# Driver.net
KiCad netlist of a schematic drawn in EAGLE
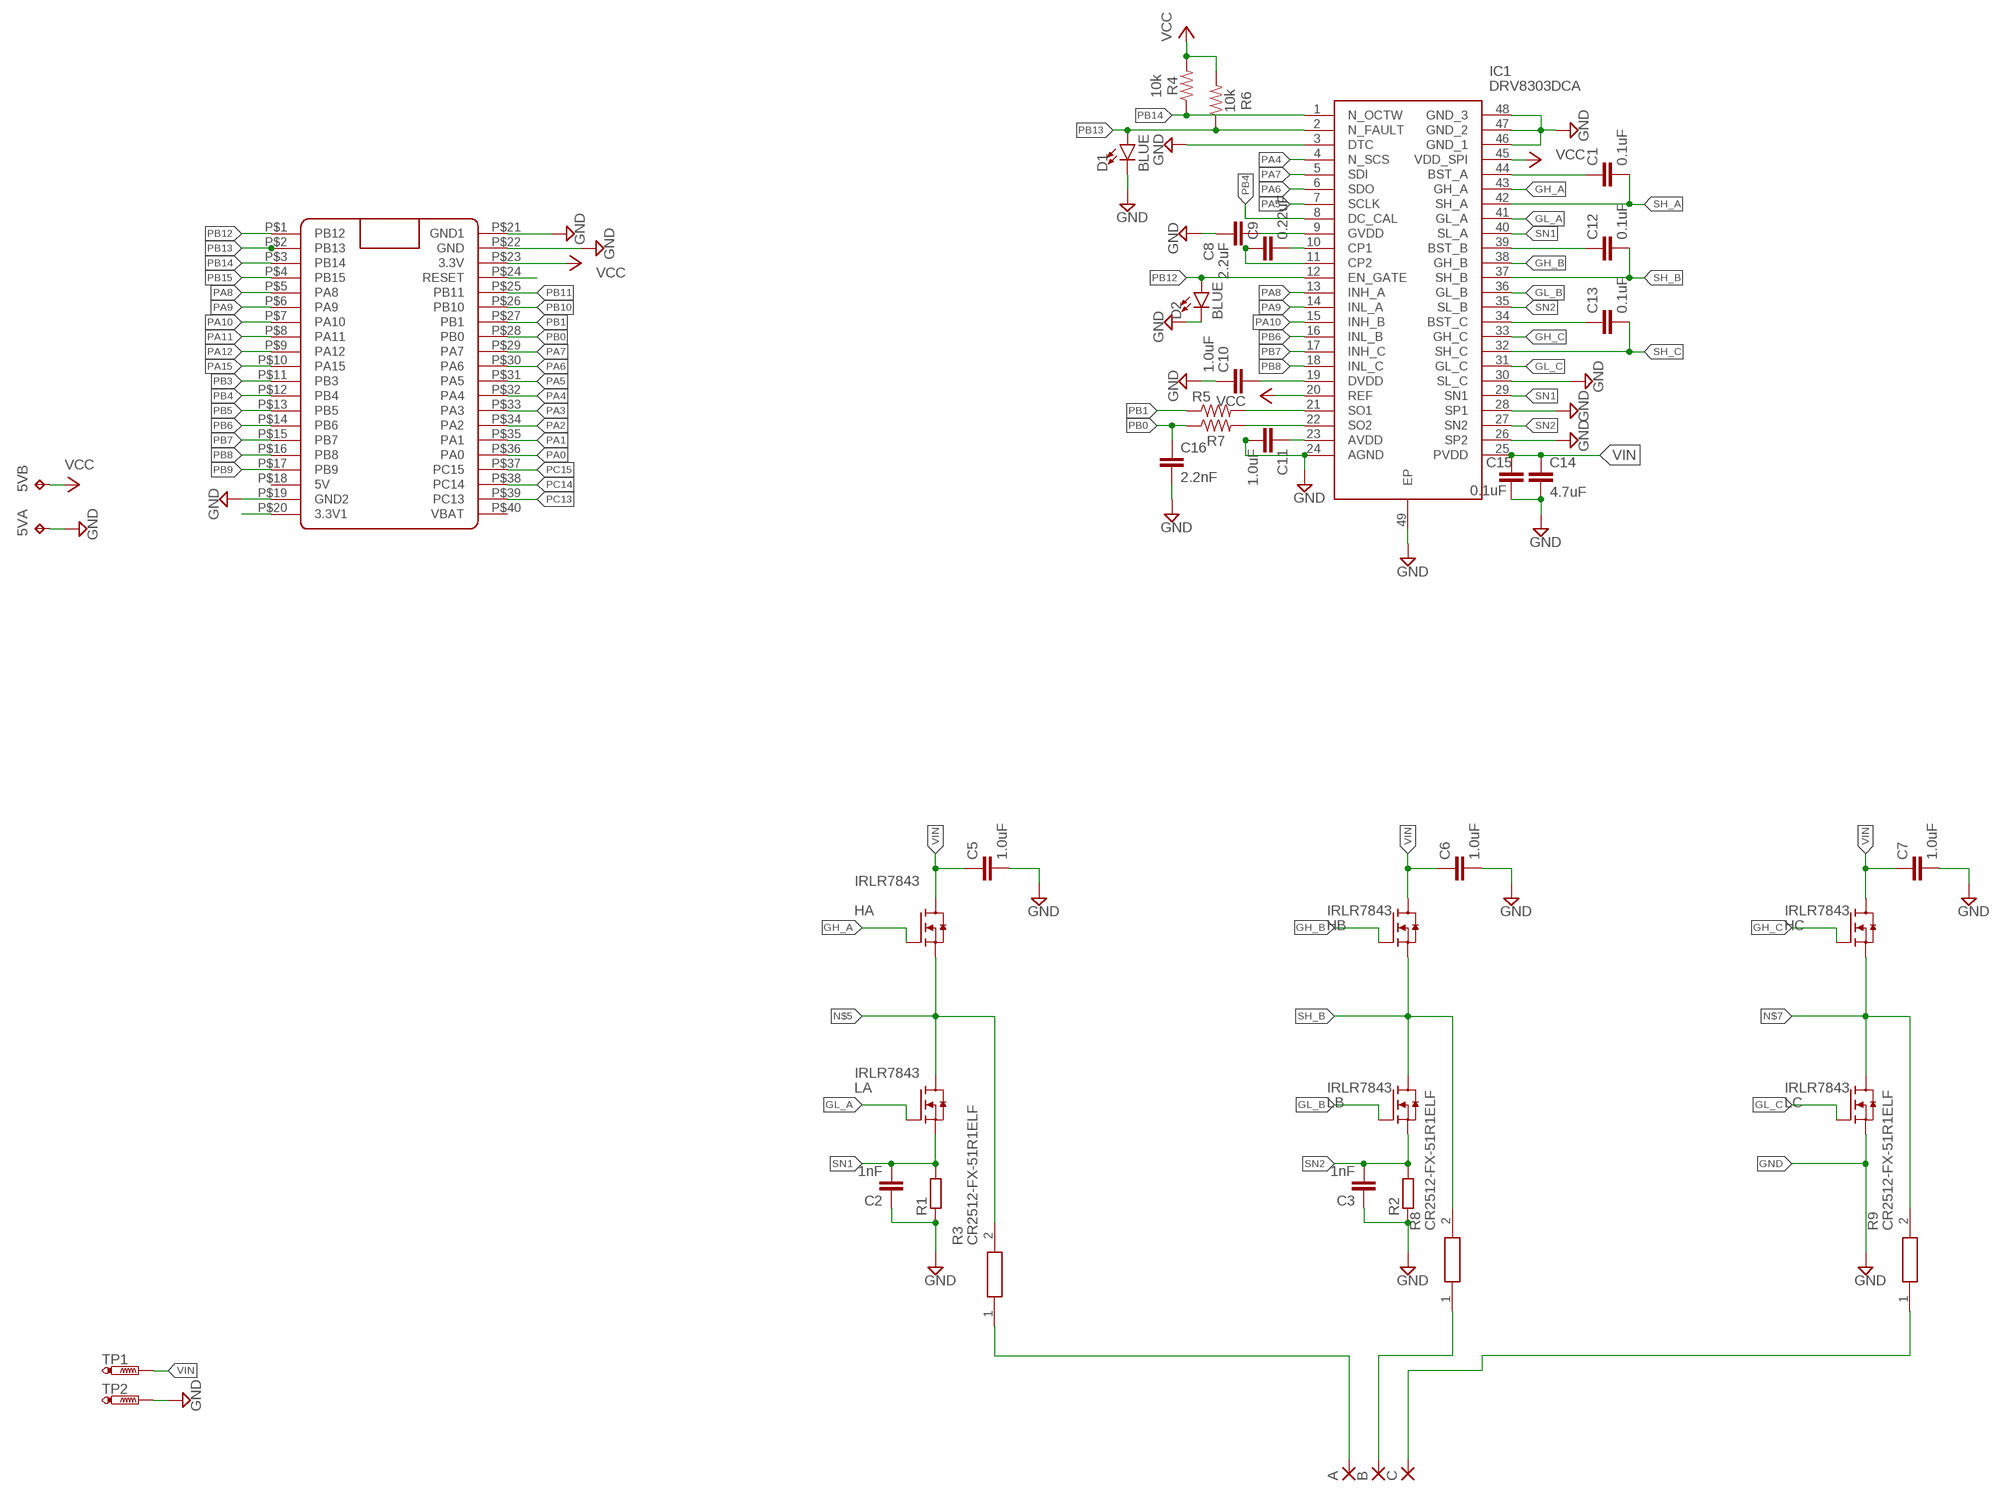
[diagram p0: schematic, sheet 1]

(export (version "E")
  (design (tool "Eeschema 10.0.6"))
  (components
    (comp (ref "5V")
      (value "TP2P2-38-17")
      (footprint "eagle-import:P2-38-17")
      (libsource (lib "eagle-import") (part "TP2P2-38-17"))
    )
    (comp (ref "A")
      (value "SMD5")
      (footprint "eagle-import:SMD2,54-5,08")
      (libsource (lib "eagle-import") (part "SMD5"))
    )
    (comp (ref "B")
      (value "SMD5")
      (footprint "eagle-import:SMD2,54-5,08")
      (libsource (lib "eagle-import") (part "SMD5"))
    )
    (comp (ref "C")
      (value "SMD5")
      (footprint "eagle-import:SMD2,54-5,08")
      (libsource (lib "eagle-import") (part "SMD5"))
    )
    (comp (ref "C1")
      (value "0.1uF")
      (footprint "eagle-import:0603")
      (libsource (lib "eagle-import") (part "0.1UF-0603-25V-(+80/-20%)"))
    )
    (comp (ref "C2")
      (value "1nF")
      (footprint "eagle-import:0603")
      (libsource (lib "eagle-import") (part "1.0NF/1000PF-0603-50V-10%"))
    )
    (comp (ref "C3")
      (value "1nF")
      (footprint "eagle-import:0603")
      (libsource (lib "eagle-import") (part "1.0NF/1000PF-0603-50V-10%"))
    )
    (comp (ref "C5")
      (value "1.0uF")
      (footprint "eagle-import:0603")
      (libsource (lib "eagle-import") (part "1.0UF-0603-16V-10%-X7R"))
    )
    (comp (ref "C6")
      (value "1.0uF")
      (footprint "eagle-import:0603")
      (libsource (lib "eagle-import") (part "1.0UF-0603-16V-10%-X7R"))
    )
    (comp (ref "C7")
      (value "1.0uF")
      (footprint "eagle-import:0603")
      (libsource (lib "eagle-import") (part "1.0UF-0603-16V-10%-X7R"))
    )
    (comp (ref "C8")
      (value "2.2uF")
      (footprint "eagle-import:0603")
      (libsource (lib "eagle-import") (part "2.2UF-0603-10V-20%"))
    )
    (comp (ref "C9")
      (value "0.22uF")
      (footprint "eagle-import:0603")
      (libsource (lib "eagle-import") (part "0.22UF-0603-25V-10%"))
    )
    (comp (ref "C10")
      (value "1.0uF")
      (footprint "eagle-import:0603")
      (libsource (lib "eagle-import") (part "1.0UF-0603-16V-10%"))
    )
    (comp (ref "C11")
      (value "1.0uF")
      (footprint "eagle-import:0603")
      (libsource (lib "eagle-import") (part "1.0UF-0603-16V-10%"))
    )
    (comp (ref "C12")
      (value "0.1uF")
      (footprint "eagle-import:0603")
      (libsource (lib "eagle-import") (part "0.1UF-0603-25V-(+80/-20%)"))
    )
    (comp (ref "C13")
      (value "0.1uF")
      (footprint "eagle-import:0603")
      (libsource (lib "eagle-import") (part "0.1UF-0603-25V-(+80/-20%)"))
    )
    (comp (ref "C14")
      (value "4.7uF")
      (footprint "eagle-import:0603")
      (libsource (lib "eagle-import") (part "4.7UF-0603-35V-(20%)"))
    )
    (comp (ref "C15")
      (value "0.1uF")
      (footprint "eagle-import:0603")
      (libsource (lib "eagle-import") (part "0.1UF-0603-25V-(+80/-20%)"))
    )
    (comp (ref "C16")
      (value "2.2nF")
      (footprint "eagle-import:0603")
      (libsource (lib "eagle-import") (part "2.2NF/2200PF-0603-50V-10%"))
    )
    (comp (ref "D1")
      (value "BLUE")
      (footprint "eagle-import:LED-0603")
      (libsource (lib "eagle-import") (part "LED-BLUE0603"))
    )
    (comp (ref "D2")
      (value "BLUE")
      (footprint "eagle-import:LED-0603")
      (libsource (lib "eagle-import") (part "LED-BLUE0603"))
    )
    (comp (ref "HA")
      (value "IRLR7843")
      (footprint "eagle-import:TO252")
      (libsource (lib "eagle-import") (part "IRLR7843"))
    )
    (comp (ref "HB")
      (value "IRLR7843")
      (footprint "eagle-import:TO252")
      (libsource (lib "eagle-import") (part "IRLR7843"))
    )
    (comp (ref "HC")
      (value "IRLR7843")
      (footprint "eagle-import:TO252")
      (libsource (lib "eagle-import") (part "IRLR7843"))
    )
    (comp (ref "IC1")
      (value "DRV8303DCA")
      (footprint "eagle-import:SOP50P810X120-49N")
      (fields (field (name "MOUSER_PART_NUMBER") "595-DRV8303DCA"))
      (libsource (lib "eagle-import") (part "DRV8303DCA"))
    )
    (comp (ref "LA")
      (value "IRLR7843")
      (footprint "eagle-import:TO252")
      (libsource (lib "eagle-import") (part "IRLR7843"))
    )
    (comp (ref "LB")
      (value "IRLR7843")
      (footprint "eagle-import:TO252")
      (libsource (lib "eagle-import") (part "IRLR7843"))
    )
    (comp (ref "LC")
      (value "IRLR7843")
      (footprint "eagle-import:TO252")
      (libsource (lib "eagle-import") (part "IRLR7843"))
    )
    (comp (ref "R1")
      (value "R-EU_R2512")
      (footprint "eagle-import:R2512")
      (libsource (lib "eagle-import") (part "R-EU_R2512"))
    )
    (comp (ref "R2")
      (value "R-EU_R2512")
      (footprint "eagle-import:R2512")
      (libsource (lib "eagle-import") (part "R-EU_R2512"))
    )
    (comp (ref "R3")
      (value "CR2512-FX-51R1ELF")
      (footprint "eagle-import:RESC6331X75N")
      (fields (field (name "MOUSER_PART_NUMBER") "652-CR2512FX51R1ELF"))
      (libsource (lib "eagle-import") (part "CR2512-FX-51R1ELF"))
    )
    (comp (ref "R4")
      (value "10k")
      (footprint "eagle-import:0603")
      (libsource (lib "eagle-import") (part "10KOHM-0603-1/10W-1%"))
    )
    (comp (ref "R5")
      (value "0")
      (footprint "eagle-import:0603")
      (libsource (lib "eagle-import") (part "0OHM-0603-1/10W"))
    )
    (comp (ref "R6")
      (value "10k")
      (footprint "eagle-import:0603")
      (libsource (lib "eagle-import") (part "10KOHM-0603-1/10W-1%"))
    )
    (comp (ref "R7")
      (value "0")
      (footprint "eagle-import:0603")
      (libsource (lib "eagle-import") (part "0OHM-0603-1/10W"))
    )
    (comp (ref "R8")
      (value "CR2512-FX-51R1ELF")
      (footprint "eagle-import:RESC6331X75N")
      (fields (field (name "MOUSER_PART_NUMBER") "652-CR2512FX51R1ELF"))
      (libsource (lib "eagle-import") (part "CR2512-FX-51R1ELF"))
    )
    (comp (ref "R9")
      (value "CR2512-FX-51R1ELF")
      (footprint "eagle-import:RESC6331X75N")
      (fields (field (name "MOUSER_PART_NUMBER") "652-CR2512FX51R1ELF"))
      (libsource (lib "eagle-import") (part "CR2512-FX-51R1ELF"))
    )
    (comp (ref "TP1")
      (value "PTR1PAD1-20Y")
      (footprint "eagle-import:P1-20Y")
      (libsource (lib "eagle-import") (part "PTR1PAD1-20Y"))
    )
    (comp (ref "TP2")
      (value "PTR1PAD1-20Y")
      (footprint "eagle-import:P1-20Y")
      (libsource (lib "eagle-import") (part "PTR1PAD1-20Y"))
    )
    (comp (ref "U$1")
      (value "BLUE_PILLADVANCED")
      (footprint "eagle-import:BLUE_PILL_ADV")
      (libsource (lib "eagle-import") (part "BLUE_PILLADVANCED"))
    )
  )
  (nets
    (net (code "1") (name "GH_A") (class "Default")
      (node (ref "HA") (pin "1") (pinfunction "G_1") (pintype "passive"))
      (node (ref "IC1") (pin "43") (pinfunction "GH_A_43") (pintype "output"))
    )
    (net (code "2") (name "GH_B") (class "Default")
      (node (ref "HB") (pin "1") (pinfunction "G_1") (pintype "passive"))
      (node (ref "IC1") (pin "38") (pinfunction "GH_B_38") (pintype "output"))
    )
    (net (code "3") (name "GH_C") (class "Default")
      (node (ref "HC") (pin "1") (pinfunction "G_1") (pintype "passive"))
      (node (ref "IC1") (pin "33") (pinfunction "GH_C_33") (pintype "output"))
    )
    (net (code "4") (name "GL_A") (class "Default")
      (node (ref "IC1") (pin "41") (pinfunction "GL_A_41") (pintype "output"))
      (node (ref "LA") (pin "1") (pinfunction "G_1") (pintype "passive"))
    )
    (net (code "5") (name "GL_B") (class "Default")
      (node (ref "IC1") (pin "36") (pinfunction "GL_B_36") (pintype "output"))
      (node (ref "LB") (pin "1") (pinfunction "G_1") (pintype "passive"))
    )
    (net (code "6") (name "GL_C") (class "Default")
      (node (ref "IC1") (pin "31") (pinfunction "GL_C_31") (pintype "output"))
      (node (ref "LC") (pin "1") (pinfunction "G_1") (pintype "passive"))
    )
    (net (code "7") (name "GND") (class "Default")
      (node (ref "5V") (pin "TP-1") (pinfunction "TP_TP-1") (pintype "input"))
      (node (ref "C10") (pin "1") (pinfunction "1_1") (pintype "passive"))
      (node (ref "C11") (pin "2") (pinfunction "2_2") (pintype "passive"))
      (node (ref "C14") (pin "2") (pinfunction "2_2") (pintype "passive"))
      (node (ref "C15") (pin "2") (pinfunction "2_2") (pintype "passive"))
      (node (ref "C16") (pin "2") (pinfunction "2_2") (pintype "passive"))
      (node (ref "C2") (pin "1") (pinfunction "1_1") (pintype "passive"))
      (node (ref "C3") (pin "1") (pinfunction "1_1") (pintype "passive"))
      (node (ref "C5") (pin "2") (pinfunction "2_2") (pintype "passive"))
      (node (ref "C6") (pin "2") (pinfunction "2_2") (pintype "passive"))
      (node (ref "C7") (pin "2") (pinfunction "2_2") (pintype "passive"))
      (node (ref "C8") (pin "2") (pinfunction "2_2") (pintype "passive"))
      (node (ref "D1") (pin "C") (pinfunction "C_C") (pintype "passive"))
      (node (ref "D2") (pin "C") (pinfunction "C_C") (pintype "passive"))
      (node (ref "IC1") (pin "24") (pinfunction "AGND_24") (pintype "power_in"))
      (node (ref "IC1") (pin "26") (pinfunction "SP2_26") (pintype "input"))
      (node (ref "IC1") (pin "28") (pinfunction "SP1_28") (pintype "input"))
      (node (ref "IC1") (pin "3") (pinfunction "DTC_3") (pintype "input"))
      (node (ref "IC1") (pin "30") (pinfunction "SL_C_30") (pintype "input"))
      (node (ref "IC1") (pin "46") (pinfunction "GND_1_46") (pintype "power_in"))
      (node (ref "IC1") (pin "47") (pinfunction "GND_2_47") (pintype "power_in"))
      (node (ref "IC1") (pin "48") (pinfunction "GND_3_48") (pintype "power_in"))
      (node (ref "IC1") (pin "49") (pinfunction "EP_49") (pintype "bidirectional"))
      (node (ref "LC") (pin "2") (pinfunction "S_2") (pintype "passive"))
      (node (ref "R1") (pin "1") (pinfunction "1_1") (pintype "passive"))
      (node (ref "R2") (pin "1") (pinfunction "1_1") (pintype "passive"))
      (node (ref "TP2") (pin "TP") (pinfunction "TP_TP") (pintype "input"))
      (node (ref "U$1") (pin "P$19") (pinfunction "GND2_P$19") (pintype "bidirectional"))
      (node (ref "U$1") (pin "P$21") (pinfunction "GND1_P$21") (pintype "power_in"))
      (node (ref "U$1") (pin "P$22") (pinfunction "GND_P$22") (pintype "bidirectional"))
    )
    (net (code "8") (name "N$5") (class "Default")
      (node (ref "HA") (pin "2") (pinfunction "S_2") (pintype "passive"))
      (node (ref "LA") (pin "3") (pinfunction "D_3") (pintype "passive"))
      (node (ref "R3") (pin "2") (pinfunction "2_2") (pintype "bidirectional"))
    )
    (net (code "9") (name "N$7") (class "Default")
      (node (ref "HC") (pin "2") (pinfunction "S_2") (pintype "passive"))
      (node (ref "LC") (pin "3") (pinfunction "D_3") (pintype "passive"))
      (node (ref "R9") (pin "2") (pinfunction "2_2") (pintype "bidirectional"))
    )
    (net (code "10") (name "Net-(B-P)") (class "Default")
      (node (ref "B") (pin "1") (pinfunction "P_1") (pintype "passive"))
      (node (ref "R8") (pin "1") (pinfunction "1_1") (pintype "bidirectional"))
    )
    (net (code "11") (name "Net-(IC1-AVDD)") (class "Default")
      (node (ref "C11") (pin "1") (pinfunction "1_1") (pintype "passive"))
      (node (ref "IC1") (pin "23") (pinfunction "AVDD_23") (pintype "power_in"))
    )
    (net (code "12") (name "Net-(IC1-BST_A)") (class "Default")
      (node (ref "C1") (pin "1") (pinfunction "1_1") (pintype "passive"))
      (node (ref "IC1") (pin "44") (pinfunction "BST_A_44") (pintype "bidirectional"))
    )
    (net (code "13") (name "Net-(IC1-BST_B)") (class "Default")
      (node (ref "C12") (pin "1") (pinfunction "1_1") (pintype "passive"))
      (node (ref "IC1") (pin "39") (pinfunction "BST_B_39") (pintype "bidirectional"))
    )
    (net (code "14") (name "Net-(IC1-BST_C)") (class "Default")
      (node (ref "C13") (pin "1") (pinfunction "1_1") (pintype "passive"))
      (node (ref "IC1") (pin "34") (pinfunction "BST_C_34") (pintype "bidirectional"))
    )
    (net (code "15") (name "Net-(IC1-CP1)") (class "Default")
      (node (ref "C9") (pin "2") (pinfunction "2_2") (pintype "passive"))
      (node (ref "IC1") (pin "10") (pinfunction "CP1_10") (pintype "power_in"))
    )
    (net (code "16") (name "Net-(IC1-CP2)") (class "Default")
      (node (ref "C9") (pin "1") (pinfunction "1_1") (pintype "passive"))
      (node (ref "IC1") (pin "11") (pinfunction "CP2_11") (pintype "power_in"))
    )
    (net (code "17") (name "Net-(IC1-DVDD)") (class "Default")
      (node (ref "C10") (pin "2") (pinfunction "2_2") (pintype "passive"))
      (node (ref "IC1") (pin "19") (pinfunction "DVDD_19") (pintype "power_in"))
    )
    (net (code "18") (name "Net-(IC1-GVDD)") (class "Default")
      (node (ref "C8") (pin "1") (pinfunction "1_1") (pintype "passive"))
      (node (ref "IC1") (pin "9") (pinfunction "GVDD_9") (pintype "power_in"))
    )
    (net (code "19") (name "Net-(IC1-SO1)") (class "Default")
      (node (ref "IC1") (pin "21") (pinfunction "SO1_21") (pintype "output"))
      (node (ref "R5") (pin "2") (pinfunction "2_2") (pintype "passive"))
    )
    (net (code "20") (name "Net-(IC1-SO2)") (class "Default")
      (node (ref "IC1") (pin "22") (pinfunction "SO2_22") (pintype "output"))
      (node (ref "R7") (pin "2") (pinfunction "2_2") (pintype "passive"))
    )
    (net (code "21") (name "PA0") (class "Default")
      (node (ref "U$1") (pin "P$36") (pinfunction "PA0_P$36") (pintype "bidirectional"))
    )
    (net (code "22") (name "PA1") (class "Default")
      (node (ref "U$1") (pin "P$35") (pinfunction "PA1_P$35") (pintype "bidirectional"))
    )
    (net (code "23") (name "PA2") (class "Default")
      (node (ref "U$1") (pin "P$34") (pinfunction "PA2_P$34") (pintype "bidirectional"))
    )
    (net (code "24") (name "PA3") (class "Default")
      (node (ref "U$1") (pin "P$33") (pinfunction "PA3_P$33") (pintype "bidirectional"))
    )
    (net (code "25") (name "PA4") (class "Default")
      (node (ref "IC1") (pin "4") (pinfunction "N_SCS_4") (pintype "input"))
      (node (ref "U$1") (pin "P$32") (pinfunction "PA4_P$32") (pintype "bidirectional"))
    )
    (net (code "26") (name "PA5") (class "Default")
      (node (ref "IC1") (pin "7") (pinfunction "SCLK_7") (pintype "input"))
      (node (ref "U$1") (pin "P$31") (pinfunction "PA5_P$31") (pintype "bidirectional"))
    )
    (net (code "27") (name "PA6") (class "Default")
      (node (ref "IC1") (pin "6") (pinfunction "SDO_6") (pintype "output"))
      (node (ref "U$1") (pin "P$30") (pinfunction "PA6_P$30") (pintype "bidirectional"))
    )
    (net (code "28") (name "PA7") (class "Default")
      (node (ref "IC1") (pin "5") (pinfunction "SDI_5") (pintype "input"))
      (node (ref "U$1") (pin "P$29") (pinfunction "PA7_P$29") (pintype "bidirectional"))
    )
    (net (code "29") (name "PA8") (class "Default")
      (node (ref "IC1") (pin "13") (pinfunction "INH_A_13") (pintype "input"))
      (node (ref "U$1") (pin "P$5") (pinfunction "PA8_P$5") (pintype "bidirectional"))
    )
    (net (code "30") (name "PA9") (class "Default")
      (node (ref "IC1") (pin "14") (pinfunction "INL_A_14") (pintype "input"))
      (node (ref "U$1") (pin "P$6") (pinfunction "PA9_P$6") (pintype "bidirectional"))
    )
    (net (code "31") (name "PA10") (class "Default")
      (node (ref "IC1") (pin "15") (pinfunction "INH_B_15") (pintype "input"))
      (node (ref "U$1") (pin "P$7") (pinfunction "PA10_P$7") (pintype "bidirectional"))
    )
    (net (code "32") (name "PA11") (class "Default")
      (node (ref "U$1") (pin "P$8") (pinfunction "PA11_P$8") (pintype "bidirectional"))
    )
    (net (code "33") (name "PA12") (class "Default")
      (node (ref "U$1") (pin "P$9") (pinfunction "PA12_P$9") (pintype "bidirectional"))
    )
    (net (code "34") (name "PA15") (class "Default")
      (node (ref "U$1") (pin "P$10") (pinfunction "PA15_P$10") (pintype "bidirectional"))
    )
    (net (code "35") (name "PB0") (class "Default")
      (node (ref "C16") (pin "1") (pinfunction "1_1") (pintype "passive"))
      (node (ref "R7") (pin "1") (pinfunction "1_1") (pintype "passive"))
      (node (ref "U$1") (pin "P$28") (pinfunction "PB0_P$28") (pintype "bidirectional"))
    )
    (net (code "36") (name "PB1") (class "Default")
      (node (ref "R5") (pin "1") (pinfunction "1_1") (pintype "passive"))
      (node (ref "U$1") (pin "P$27") (pinfunction "PB1_P$27") (pintype "bidirectional"))
    )
    (net (code "37") (name "PB3") (class "Default")
      (node (ref "U$1") (pin "P$11") (pinfunction "PB3_P$11") (pintype "bidirectional"))
    )
    (net (code "38") (name "PB4") (class "Default")
      (node (ref "IC1") (pin "8") (pinfunction "DC_CAL_8") (pintype "input"))
      (node (ref "U$1") (pin "P$12") (pinfunction "PB4_P$12") (pintype "bidirectional"))
    )
    (net (code "39") (name "PB5") (class "Default")
      (node (ref "U$1") (pin "P$13") (pinfunction "PB5_P$13") (pintype "bidirectional"))
    )
    (net (code "40") (name "PB6") (class "Default")
      (node (ref "IC1") (pin "16") (pinfunction "INL_B_16") (pintype "input"))
      (node (ref "U$1") (pin "P$14") (pinfunction "PB6_P$14") (pintype "bidirectional"))
    )
    (net (code "41") (name "PB7") (class "Default")
      (node (ref "IC1") (pin "17") (pinfunction "INH_C_17") (pintype "input"))
      (node (ref "U$1") (pin "P$15") (pinfunction "PB7_P$15") (pintype "bidirectional"))
    )
    (net (code "42") (name "PB8") (class "Default")
      (node (ref "IC1") (pin "18") (pinfunction "INL_C_18") (pintype "input"))
      (node (ref "U$1") (pin "P$16") (pinfunction "PB8_P$16") (pintype "bidirectional"))
    )
    (net (code "43") (name "PB9") (class "Default")
      (node (ref "U$1") (pin "P$17") (pinfunction "PB9_P$17") (pintype "bidirectional"))
    )
    (net (code "44") (name "PB10") (class "Default")
      (node (ref "U$1") (pin "P$26") (pinfunction "PB10_P$26") (pintype "bidirectional"))
    )
    (net (code "45") (name "PB11") (class "Default")
      (node (ref "U$1") (pin "P$25") (pinfunction "PB11_P$25") (pintype "bidirectional"))
    )
    (net (code "46") (name "PB12") (class "Default")
      (node (ref "D2") (pin "A") (pinfunction "A_A") (pintype "passive"))
      (node (ref "IC1") (pin "12") (pinfunction "EN_GATE_12") (pintype "input"))
      (node (ref "U$1") (pin "P$1") (pinfunction "PB12_P$1") (pintype "bidirectional"))
    )
    (net (code "47") (name "PB13") (class "Default")
      (node (ref "D1") (pin "A") (pinfunction "A_A") (pintype "passive"))
      (node (ref "IC1") (pin "2") (pinfunction "N_FAULT_2") (pintype "output"))
      (node (ref "R6") (pin "1") (pinfunction "1_1") (pintype "passive"))
      (node (ref "U$1") (pin "P$2") (pinfunction "PB13_P$2") (pintype "bidirectional"))
    )
    (net (code "48") (name "PB14") (class "Default")
      (node (ref "IC1") (pin "1") (pinfunction "N_OCTW_1") (pintype "output"))
      (node (ref "R4") (pin "1") (pinfunction "1_1") (pintype "passive"))
      (node (ref "U$1") (pin "P$3") (pinfunction "PB14_P$3") (pintype "bidirectional"))
    )
    (net (code "49") (name "PB15") (class "Default")
      (node (ref "U$1") (pin "P$4") (pinfunction "PB15_P$4") (pintype "bidirectional"))
    )
    (net (code "50") (name "PC13") (class "Default")
      (node (ref "U$1") (pin "P$39") (pinfunction "PC13_P$39") (pintype "bidirectional"))
    )
    (net (code "51") (name "PC14") (class "Default")
      (node (ref "U$1") (pin "P$38") (pinfunction "PC14_P$38") (pintype "bidirectional"))
    )
    (net (code "52") (name "PC15") (class "Default")
      (node (ref "U$1") (pin "P$37") (pinfunction "PC15_P$37") (pintype "bidirectional"))
    )
    (net (code "53") (name "SH_A") (class "Default")
      (node (ref "A") (pin "1") (pinfunction "P_1") (pintype "passive"))
      (node (ref "C1") (pin "2") (pinfunction "2_2") (pintype "passive"))
      (node (ref "IC1") (pin "42") (pinfunction "SH_A_42") (pintype "input"))
      (node (ref "R3") (pin "1") (pinfunction "1_1") (pintype "bidirectional"))
    )
    (net (code "54") (name "SH_B") (class "Default")
      (node (ref "C12") (pin "2") (pinfunction "2_2") (pintype "passive"))
      (node (ref "HB") (pin "2") (pinfunction "S_2") (pintype "passive"))
      (node (ref "IC1") (pin "37") (pinfunction "SH_B_37") (pintype "input"))
      (node (ref "LB") (pin "3") (pinfunction "D_3") (pintype "passive"))
      (node (ref "R8") (pin "2") (pinfunction "2_2") (pintype "bidirectional"))
    )
    (net (code "55") (name "SH_C") (class "Default")
      (node (ref "C") (pin "1") (pinfunction "P_1") (pintype "passive"))
      (node (ref "C13") (pin "2") (pinfunction "2_2") (pintype "passive"))
      (node (ref "IC1") (pin "32") (pinfunction "SH_C_32") (pintype "input"))
      (node (ref "R9") (pin "1") (pinfunction "1_1") (pintype "bidirectional"))
    )
    (net (code "56") (name "SN1") (class "Default")
      (node (ref "C2") (pin "2") (pinfunction "2_2") (pintype "passive"))
      (node (ref "IC1") (pin "29") (pinfunction "SN1_29") (pintype "input"))
      (node (ref "IC1") (pin "40") (pinfunction "SL_A_40") (pintype "input"))
      (node (ref "LA") (pin "2") (pinfunction "S_2") (pintype "passive"))
      (node (ref "R1") (pin "2") (pinfunction "2_2") (pintype "passive"))
    )
    (net (code "57") (name "SN2") (class "Default")
      (node (ref "C3") (pin "2") (pinfunction "2_2") (pintype "passive"))
      (node (ref "IC1") (pin "27") (pinfunction "SN2_27") (pintype "input"))
      (node (ref "IC1") (pin "35") (pinfunction "SL_B_35") (pintype "input"))
      (node (ref "LB") (pin "2") (pinfunction "S_2") (pintype "passive"))
      (node (ref "R2") (pin "2") (pinfunction "2_2") (pintype "passive"))
    )
    (net (code "58") (name "VCC") (class "Default")
      (node (ref "5V") (pin "TP-2") (pinfunction "TP_TP-2") (pintype "input"))
      (node (ref "IC1") (pin "20") (pinfunction "REF_20") (pintype "input"))
      (node (ref "IC1") (pin "45") (pinfunction "VDD_SPI_45") (pintype "power_in"))
      (node (ref "R4") (pin "2") (pinfunction "2_2") (pintype "passive"))
      (node (ref "R6") (pin "2") (pinfunction "2_2") (pintype "passive"))
      (node (ref "U$1") (pin "P$23") (pinfunction "3.3V_P$23") (pintype "bidirectional"))
    )
    (net (code "59") (name "VIN") (class "Default")
      (node (ref "C14") (pin "1") (pinfunction "1_1") (pintype "passive"))
      (node (ref "C15") (pin "1") (pinfunction "1_1") (pintype "passive"))
      (node (ref "C5") (pin "1") (pinfunction "1_1") (pintype "passive"))
      (node (ref "C6") (pin "1") (pinfunction "1_1") (pintype "passive"))
      (node (ref "C7") (pin "1") (pinfunction "1_1") (pintype "passive"))
      (node (ref "HA") (pin "3") (pinfunction "D_3") (pintype "passive"))
      (node (ref "HB") (pin "3") (pinfunction "D_3") (pintype "passive"))
      (node (ref "HC") (pin "3") (pinfunction "D_3") (pintype "passive"))
      (node (ref "IC1") (pin "25") (pinfunction "PVDD_25") (pintype "power_in"))
      (node (ref "TP1") (pin "TP") (pinfunction "TP_TP") (pintype "input"))
    )
    (net (code "60") (name "unconnected-(U$1-3.3V1-PadP$20)") (class "Default")
      (node (ref "U$1") (pin "P$20") (pinfunction "3.3V1_P$20") (pintype "bidirectional"))
    )
    (net (code "61") (name "unconnected-(U$1-5V-PadP$18)") (class "Default")
      (node (ref "U$1") (pin "P$18") (pinfunction "5V_P$18") (pintype "bidirectional"))
    )
    (net (code "62") (name "unconnected-(U$1-RESET-PadP$24)") (class "Default")
      (node (ref "U$1") (pin "P$24") (pinfunction "RESET_P$24") (pintype "bidirectional"))
    )
    (net (code "63") (name "unconnected-(U$1-VBAT-PadP$40)") (class "Default")
      (node (ref "U$1") (pin "P$40") (pinfunction "VBAT_P$40") (pintype "bidirectional"))
    )
  )
)
